# current_switch.net
KiCad netlist of a schematic drawn in Altium Designer
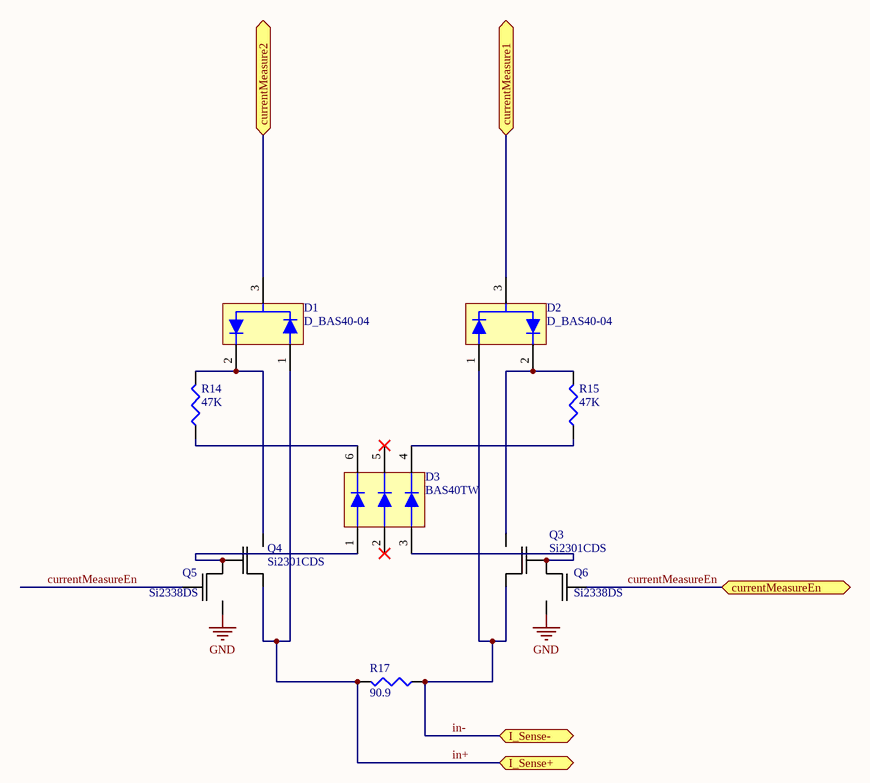
[diagram p0: current_switch.SchDoc]

(export (version "E")
  (design (tool "Eeschema 10.0.6"))
  (components
    (comp (ref "D1")
      (value "D_BAS40-04")
      (footprint "SOT23-3")
      (description "SURFACE MOUNT SCHOTTKY BARRIER DIODE")
      (libsource (lib "rlc") (part "D_BAS40-04"))
    )
    (comp (ref "D2")
      (value "D_BAS40-04")
      (footprint "SOT23-3")
      (description "SURFACE MOUNT SCHOTTKY BARRIER DIODE")
      (libsource (lib "") (part "D_BAS40-04_1"))
    )
    (comp (ref "D3")
      (value "BAS40TW")
      (footprint "SOT-363")
      (description "SURFACE MOUNT SCHOTTKY BARRIER DIODE ARRAYS")
      (libsource (lib "rlc") (part "D_BAS40TW"))
    )
    (comp (ref "Q3")
      (value "Si2301CDS")
      (footprint "SOT23-3")
      (description "P-Channel 20 V (D-S) MOSFET")
      (libsource (lib "transistors") (part "Si2301CDS"))
    )
    (comp (ref "Q4")
      (value "Si2301CDS")
      (footprint "SOT23-3")
      (description "P-Channel 20 V (D-S) MOSFET")
      (libsource (lib "transistors") (part "Si2301CDS"))
    )
    (comp (ref "Q5")
      (value "Si2338DS")
      (footprint "SOT23-3")
      (description "N-Channel 30 V (D-S) MOSFET")
      (libsource (lib "transistors") (part "Si2338DS"))
    )
    (comp (ref "Q6")
      (value "Si2338DS")
      (footprint "SOT23-3")
      (description "N-Channel 30 V (D-S) MOSFET")
      (libsource (lib "transistors") (part "Si2338DS"))
    )
    (comp (ref "R14")
      (value "47K")
      (footprint "0402")
      (description "Chip resistor, 47K, 0402 package")
      (fields (field (name "TOLERANCE") "1%") (field (name "POWER") "1/16 W"))
      (libsource (lib "rlc") (part "R_47K_0402"))
    )
    (comp (ref "R15")
      (value "47K")
      (footprint "0402")
      (description "Chip resistor, 47K, 0402 package")
      (fields (field (name "TOLERANCE") "1%") (field (name "POWER") "1/16 W"))
      (libsource (lib "rlc") (part "R_47K_0402"))
    )
    (comp (ref "R17")
      (value "90.9")
      (footprint "0603")
      (description "Chip resistor, 90.9, 0603 package")
      (fields (field (name "TOLERANCE") "0.1%") (field (name "POWER") "1/10 W"))
      (libsource (lib "rlc") (part "R_90.9_0603"))
    )
  )
  (nets
    (net (code "1") (name "/currentMeasure1") (class "Default")
      (node (ref "D2") (pin "3") (pinfunction "3_3") (pintype "passive"))
    )
    (net (code "2") (name "/currentMeasure2") (class "Default")
      (node (ref "D1") (pin "3") (pinfunction "3_3") (pintype "passive"))
    )
    (net (code "3") (name "/currentMeasureEn") (class "Default")
      (node (ref "Q5") (pin "1") (pinfunction "G_1") (pintype "passive"))
      (node (ref "Q6") (pin "1") (pinfunction "G_1") (pintype "passive"))
    )
    (net (code "4") (name "/in+") (class "Default")
      (node (ref "D1") (pin "1") (pinfunction "1_1") (pintype "passive"))
      (node (ref "Q4") (pin "3") (pinfunction "D_3") (pintype "passive"))
      (node (ref "R17") (pin "1") (pintype "passive"))
    )
    (net (code "5") (name "/in-") (class "Default")
      (node (ref "D2") (pin "1") (pinfunction "1_1") (pintype "passive"))
      (node (ref "Q3") (pin "3") (pinfunction "D_3") (pintype "passive"))
      (node (ref "R17") (pin "2") (pintype "passive"))
    )
    (net (code "6") (name "GND") (class "Default")
      (node (ref "Q5") (pin "2") (pinfunction "S_2") (pintype "passive"))
      (node (ref "Q6") (pin "2") (pinfunction "S_2") (pintype "passive"))
    )
    (net (code "7") (name "Net-(D3-Pad4)") (class "Default")
      (node (ref "D3") (pin "4") (pinfunction "4_4") (pintype "passive"))
      (node (ref "R15") (pin "2") (pintype "passive"))
    )
    (net (code "8") (name "Net-(D3-Pad6)") (class "Default")
      (node (ref "D3") (pin "6") (pinfunction "6_6") (pintype "passive"))
      (node (ref "R14") (pin "2") (pintype "passive"))
    )
    (net (code "9") (name "Net-(Q3-G)") (class "Default")
      (node (ref "D3") (pin "3") (pinfunction "3_3") (pintype "passive"))
      (node (ref "Q3") (pin "1") (pinfunction "G_1") (pintype "passive"))
      (node (ref "Q6") (pin "3") (pinfunction "D_3") (pintype "passive"))
    )
    (net (code "10") (name "Net-(Q3-S)") (class "Default")
      (node (ref "D2") (pin "2") (pinfunction "2_2") (pintype "passive"))
      (node (ref "Q3") (pin "2") (pinfunction "S_2") (pintype "passive"))
      (node (ref "R15") (pin "1") (pintype "passive"))
    )
    (net (code "11") (name "Net-(Q4-G)") (class "Default")
      (node (ref "D3") (pin "1") (pinfunction "1_1") (pintype "passive"))
      (node (ref "Q4") (pin "1") (pinfunction "G_1") (pintype "passive"))
      (node (ref "Q5") (pin "3") (pinfunction "D_3") (pintype "passive"))
    )
    (net (code "12") (name "Net-(Q4-S)") (class "Default")
      (node (ref "D1") (pin "2") (pinfunction "2_2") (pintype "passive"))
      (node (ref "Q4") (pin "2") (pinfunction "S_2") (pintype "passive"))
      (node (ref "R14") (pin "1") (pintype "passive"))
    )
    (net (code "13") (name "unconnected-(D3-Pad2)") (class "Default")
      (node (ref "D3") (pin "2") (pinfunction "2_2") (pintype "passive+no_connect"))
    )
    (net (code "14") (name "unconnected-(D3-Pad5)") (class "Default")
      (node (ref "D3") (pin "5") (pinfunction "5_5") (pintype "passive+no_connect"))
    )
  )
)
